# JJ_BLDC_v0_2b.net
KiCad netlist of a schematic drawn in EAGLE
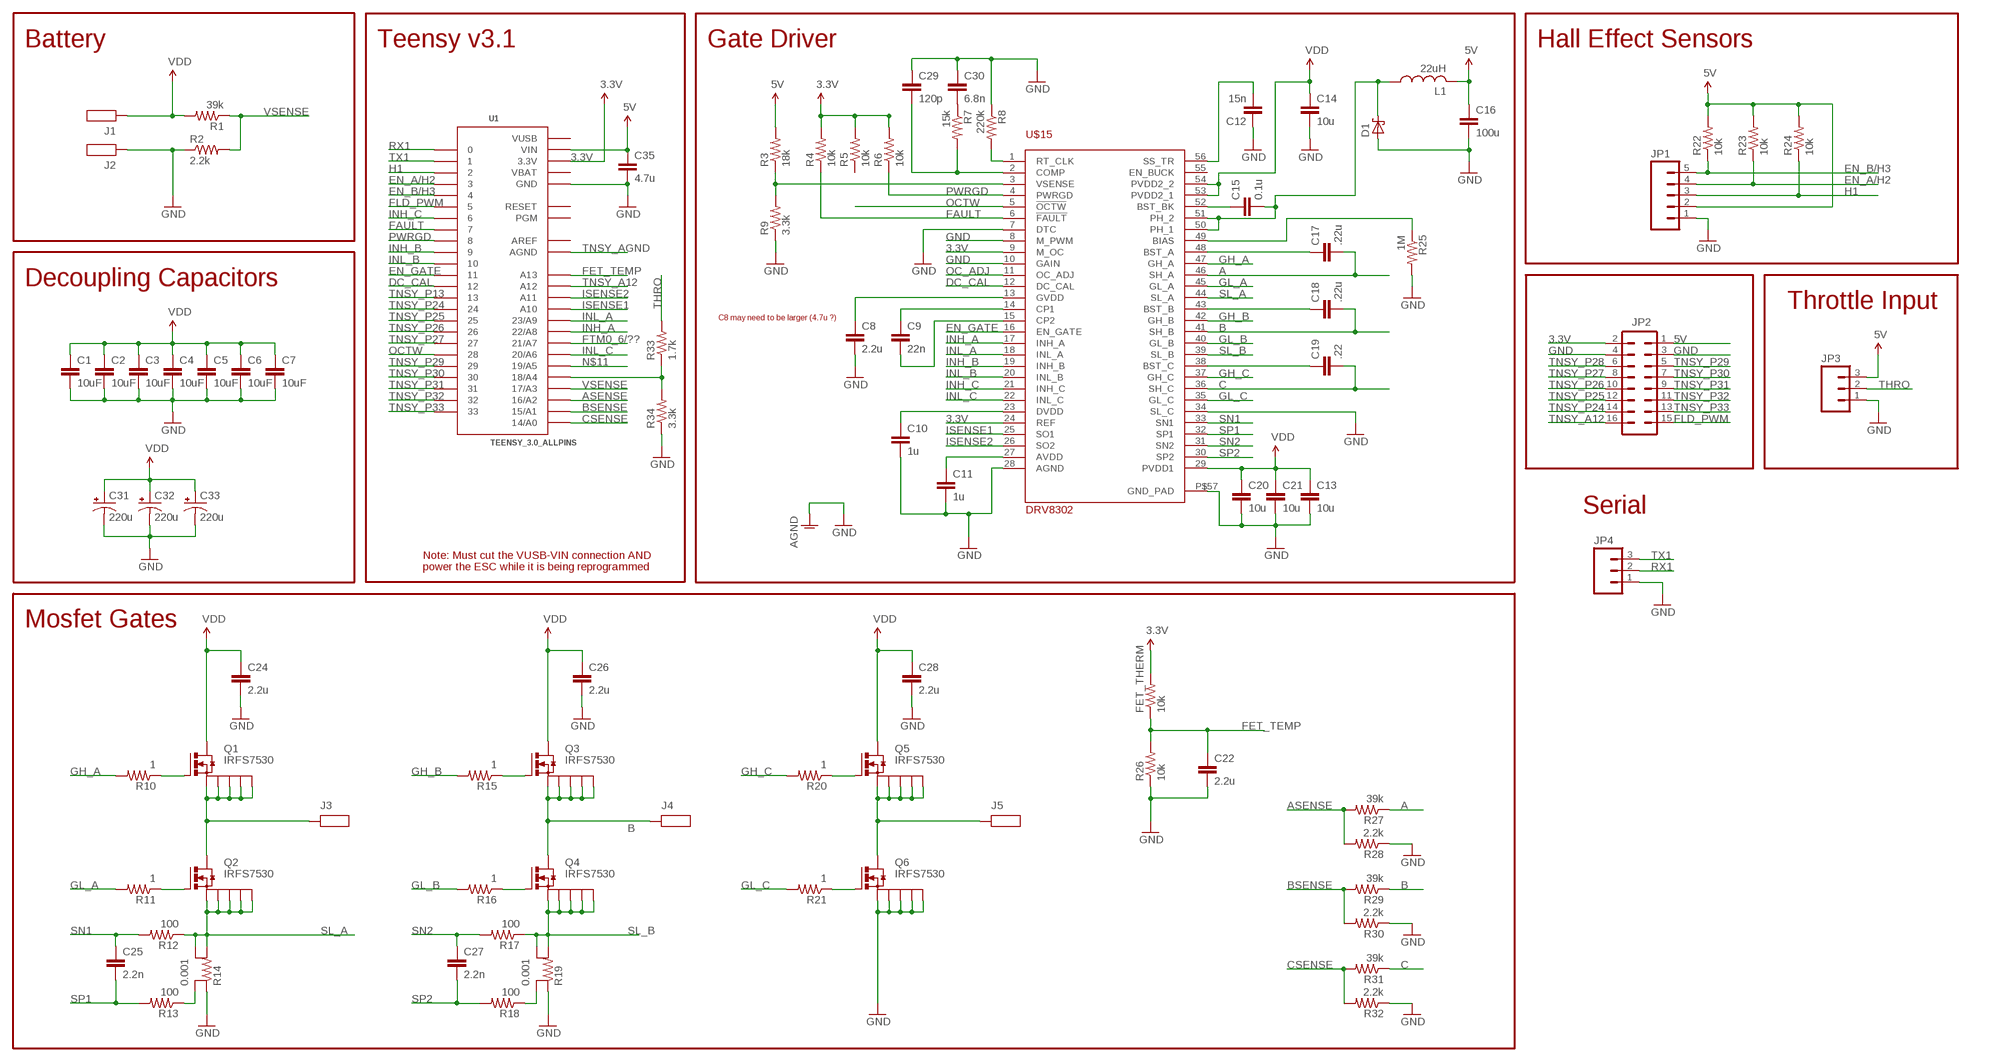
[diagram p0: schematic, sheet 1]

(export (version "E")
  (design (tool "Eeschema 10.0.6"))
  (components
    (comp (ref "C1")
      (value "10uF")
      (footprint "eagle-import:1206")
      (libsource (lib "eagle-import") (part "CAP1206"))
    )
    (comp (ref "C2")
      (value "10uF")
      (footprint "eagle-import:1206")
      (libsource (lib "eagle-import") (part "CAP1206"))
    )
    (comp (ref "C3")
      (value "10uF")
      (footprint "eagle-import:1206")
      (libsource (lib "eagle-import") (part "CAP1206"))
    )
    (comp (ref "C4")
      (value "10uF")
      (footprint "eagle-import:1206")
      (libsource (lib "eagle-import") (part "CAP1206"))
    )
    (comp (ref "C5")
      (value "10uF")
      (footprint "eagle-import:1206")
      (libsource (lib "eagle-import") (part "CAP1206"))
    )
    (comp (ref "C6")
      (value "10uF")
      (footprint "eagle-import:1206")
      (libsource (lib "eagle-import") (part "CAP1206"))
    )
    (comp (ref "C7")
      (value "10uF")
      (footprint "eagle-import:1206")
      (libsource (lib "eagle-import") (part "CAP1206"))
    )
    (comp (ref "C8")
      (value "2.2u")
      (footprint "eagle-import:0603-CAP")
      (libsource (lib "eagle-import") (part "CAP0603-CAP"))
    )
    (comp (ref "C9")
      (value "22n")
      (footprint "eagle-import:0603-CAP")
      (libsource (lib "eagle-import") (part "CAP0603-CAP"))
    )
    (comp (ref "C10")
      (value "1u")
      (footprint "eagle-import:0603-CAP")
      (libsource (lib "eagle-import") (part "CAP0603-CAP"))
    )
    (comp (ref "C11")
      (value "1u")
      (footprint "eagle-import:0603-CAP")
      (libsource (lib "eagle-import") (part "CAP0603-CAP"))
    )
    (comp (ref "C12")
      (value "15n")
      (footprint "eagle-import:0603-CAP")
      (libsource (lib "eagle-import") (part "CAP0603-CAP"))
    )
    (comp (ref "C13")
      (value "10u")
      (footprint "eagle-import:0805")
      (libsource (lib "eagle-import") (part "CAP0805"))
    )
    (comp (ref "C14")
      (value "10u")
      (footprint "eagle-import:0805")
      (libsource (lib "eagle-import") (part "CAP0805"))
    )
    (comp (ref "C15")
      (value "0.1u")
      (footprint "eagle-import:0603-CAP")
      (libsource (lib "eagle-import") (part "CAP0603-CAP"))
    )
    (comp (ref "C16")
      (value "100u")
      (footprint "eagle-import:0805")
      (libsource (lib "eagle-import") (part "CAP0805"))
    )
    (comp (ref "C17")
      (value ".22u")
      (footprint "eagle-import:0603-CAP")
      (libsource (lib "eagle-import") (part "CAP0603-CAP"))
    )
    (comp (ref "C18")
      (value ".22u")
      (footprint "eagle-import:0603-CAP")
      (libsource (lib "eagle-import") (part "CAP0603-CAP"))
    )
    (comp (ref "C19")
      (value ".22")
      (footprint "eagle-import:0603-CAP")
      (libsource (lib "eagle-import") (part "CAP0603-CAP"))
    )
    (comp (ref "C20")
      (value "10u")
      (footprint "eagle-import:0603-CAP")
      (libsource (lib "eagle-import") (part "CAP0603-CAP"))
    )
    (comp (ref "C21")
      (value "10u")
      (footprint "eagle-import:0805")
      (libsource (lib "eagle-import") (part "CAP0805"))
    )
    (comp (ref "C22")
      (value "2.2u")
      (footprint "eagle-import:0603-CAP")
      (libsource (lib "eagle-import") (part "CAP0603-CAP"))
    )
    (comp (ref "C24")
      (value "2.2u")
      (footprint "eagle-import:1206")
      (libsource (lib "eagle-import") (part "CAP1206"))
    )
    (comp (ref "C25")
      (value "2.2n")
      (footprint "eagle-import:0603-CAP")
      (libsource (lib "eagle-import") (part "CAP0603-CAP"))
    )
    (comp (ref "C26")
      (value "2.2u")
      (footprint "eagle-import:1206")
      (libsource (lib "eagle-import") (part "CAP1206"))
    )
    (comp (ref "C27")
      (value "2.2n")
      (footprint "eagle-import:0603-CAP")
      (libsource (lib "eagle-import") (part "CAP0603-CAP"))
    )
    (comp (ref "C28")
      (value "2.2u")
      (footprint "eagle-import:1206")
      (libsource (lib "eagle-import") (part "CAP1206"))
    )
    (comp (ref "C29")
      (value "120p")
      (footprint "eagle-import:0603-CAP")
      (libsource (lib "eagle-import") (part "CAP0603-CAP"))
    )
    (comp (ref "C30")
      (value "6.8n")
      (footprint "eagle-import:0603-CAP")
      (libsource (lib "eagle-import") (part "CAP0603-CAP"))
    )
    (comp (ref "C31")
      (value "220u")
      (footprint "eagle-import:E5-10,5")
      (libsource (lib "eagle-import") (part "CPOL-USE5-10.5"))
    )
    (comp (ref "C32")
      (value "220u")
      (footprint "eagle-import:E5-10,5")
      (libsource (lib "eagle-import") (part "CPOL-USE5-10.5"))
    )
    (comp (ref "C33")
      (value "220u")
      (footprint "eagle-import:E5-10,5")
      (libsource (lib "eagle-import") (part "CPOL-USE5-10.5"))
    )
    (comp (ref "C35")
      (value "4.7u")
      (footprint "eagle-import:0603-CAP")
      (libsource (lib "eagle-import") (part "CAP0603-CAP"))
    )
    (comp (ref "D1")
      (value "SCHOTTKY_SMA")
      (footprint "eagle-import:SMA")
      (libsource (lib "eagle-import") (part "SCHOTTKY_SMA"))
    )
    (comp (ref "FET_THERM")
      (value "10k")
      (footprint "eagle-import:0603-RES")
      (libsource (lib "eagle-import") (part "RESISTOR0603"))
    )
    (comp (ref "J1")
      (value "WIREPAD_SMD_10X4")
      (footprint "eagle-import:WIREPAD_SMD_10X4")
      (libsource (lib "eagle-import") (part "WIREPAD_SMD_10X4"))
    )
    (comp (ref "J2")
      (value "WIREPAD_SMD_10X4")
      (footprint "eagle-import:WIREPAD_SMD_10X4")
      (libsource (lib "eagle-import") (part "WIREPAD_SMD_10X4"))
    )
    (comp (ref "J3")
      (value "WIREPAD_SMD_10X4")
      (footprint "eagle-import:WIREPAD_SMD_10X4")
      (libsource (lib "eagle-import") (part "WIREPAD_SMD_10X4"))
    )
    (comp (ref "J4")
      (value "WIREPAD_SMD_10X4")
      (footprint "eagle-import:WIREPAD_SMD_10X4")
      (libsource (lib "eagle-import") (part "WIREPAD_SMD_10X4"))
    )
    (comp (ref "J5")
      (value "WIREPAD_SMD_10X4")
      (footprint "eagle-import:WIREPAD_SMD_10X4")
      (libsource (lib "eagle-import") (part "WIREPAD_SMD_10X4"))
    )
    (comp (ref "JP1")
      (value "M05PTH")
      (footprint "eagle-import:1X05")
      (libsource (lib "eagle-import") (part "M05PTH"))
    )
    (comp (ref "JP2")
      (value "M08X2")
      (footprint "eagle-import:2X8")
      (libsource (lib "eagle-import") (part "M08X2"))
    )
    (comp (ref "JP3")
      (value "M03PTH")
      (footprint "eagle-import:1X03")
      (libsource (lib "eagle-import") (part "M03PTH"))
    )
    (comp (ref "JP4")
      (value "M03PTH")
      (footprint "eagle-import:1X03")
      (libsource (lib "eagle-import") (part "M03PTH"))
    )
    (comp (ref "L1")
      (value "22uH")
      (footprint "eagle-import:L5650M")
      (libsource (lib "eagle-import") (part "L-USL5650M"))
    )
    (comp (ref "Q1")
      (value "IRFS7530")
      (footprint "eagle-import:TO-263-7")
      (libsource (lib "eagle-import") (part "IRFS7530"))
    )
    (comp (ref "Q2")
      (value "IRFS7530")
      (footprint "eagle-import:TO-263-7")
      (libsource (lib "eagle-import") (part "IRFS7530"))
    )
    (comp (ref "Q3")
      (value "IRFS7530")
      (footprint "eagle-import:TO-263-7")
      (libsource (lib "eagle-import") (part "IRFS7530"))
    )
    (comp (ref "Q4")
      (value "IRFS7530")
      (footprint "eagle-import:TO-263-7")
      (libsource (lib "eagle-import") (part "IRFS7530"))
    )
    (comp (ref "Q5")
      (value "IRFS7530")
      (footprint "eagle-import:TO-263-7")
      (libsource (lib "eagle-import") (part "IRFS7530"))
    )
    (comp (ref "Q6")
      (value "IRFS7530")
      (footprint "eagle-import:TO-263-7")
      (libsource (lib "eagle-import") (part "IRFS7530"))
    )
    (comp (ref "R1")
      (value "39k")
      (footprint "eagle-import:0603-RES")
      (libsource (lib "eagle-import") (part "RESISTOR0603"))
    )
    (comp (ref "R2")
      (value "2.2k")
      (footprint "eagle-import:0603-RES")
      (libsource (lib "eagle-import") (part "RESISTOR0603"))
    )
    (comp (ref "R3")
      (value "18k")
      (footprint "eagle-import:0603-RES")
      (libsource (lib "eagle-import") (part "RESISTOR0603"))
    )
    (comp (ref "R4")
      (value "10k")
      (footprint "eagle-import:0603-RES")
      (libsource (lib "eagle-import") (part "RESISTOR0603"))
    )
    (comp (ref "R5")
      (value "10k")
      (footprint "eagle-import:0603-RES")
      (libsource (lib "eagle-import") (part "RESISTOR0603"))
    )
    (comp (ref "R6")
      (value "10k")
      (footprint "eagle-import:0603-RES")
      (libsource (lib "eagle-import") (part "RESISTOR0603"))
    )
    (comp (ref "R7")
      (value "15k")
      (footprint "eagle-import:0603-RES")
      (libsource (lib "eagle-import") (part "RESISTOR0603"))
    )
    (comp (ref "R8")
      (value "220k")
      (footprint "eagle-import:0603-RES")
      (libsource (lib "eagle-import") (part "RESISTOR0603"))
    )
    (comp (ref "R9")
      (value "3.3k")
      (footprint "eagle-import:0603-RES")
      (libsource (lib "eagle-import") (part "RESISTOR0603"))
    )
    (comp (ref "R10")
      (value "1")
      (footprint "eagle-import:0603-RES")
      (libsource (lib "eagle-import") (part "RESISTOR0603"))
    )
    (comp (ref "R11")
      (value "1")
      (footprint "eagle-import:0603-RES")
      (libsource (lib "eagle-import") (part "RESISTOR0603"))
    )
    (comp (ref "R12")
      (value "100")
      (footprint "eagle-import:0603-RES")
      (libsource (lib "eagle-import") (part "RESISTOR0603"))
    )
    (comp (ref "R13")
      (value "100")
      (footprint "eagle-import:0603-RES")
      (libsource (lib "eagle-import") (part "RESISTOR0603"))
    )
    (comp (ref "R14")
      (value "0.001")
      (footprint "eagle-import:SHUNT-RES-2726")
      (libsource (lib "eagle-import") (part "WSLP2726_SHUNT"))
    )
    (comp (ref "R15")
      (value "1")
      (footprint "eagle-import:0603-RES")
      (libsource (lib "eagle-import") (part "RESISTOR0603"))
    )
    (comp (ref "R16")
      (value "1")
      (footprint "eagle-import:0603-RES")
      (libsource (lib "eagle-import") (part "RESISTOR0603"))
    )
    (comp (ref "R17")
      (value "100")
      (footprint "eagle-import:0603-RES")
      (libsource (lib "eagle-import") (part "RESISTOR0603"))
    )
    (comp (ref "R18")
      (value "100")
      (footprint "eagle-import:0603-RES")
      (libsource (lib "eagle-import") (part "RESISTOR0603"))
    )
    (comp (ref "R19")
      (value "0.001")
      (footprint "eagle-import:SHUNT-RES-2726")
      (libsource (lib "eagle-import") (part "WSLP2726_SHUNT"))
    )
    (comp (ref "R20")
      (value "1")
      (footprint "eagle-import:0603-RES")
      (libsource (lib "eagle-import") (part "RESISTOR0603"))
    )
    (comp (ref "R21")
      (value "1")
      (footprint "eagle-import:0603-RES")
      (libsource (lib "eagle-import") (part "RESISTOR0603"))
    )
    (comp (ref "R22")
      (value "10k")
      (footprint "eagle-import:0603-RES")
      (libsource (lib "eagle-import") (part "RESISTOR0603"))
    )
    (comp (ref "R23")
      (value "10k")
      (footprint "eagle-import:0603-RES")
      (libsource (lib "eagle-import") (part "RESISTOR0603"))
    )
    (comp (ref "R24")
      (value "10k")
      (footprint "eagle-import:0603-RES")
      (libsource (lib "eagle-import") (part "RESISTOR0603"))
    )
    (comp (ref "R25")
      (value "1M")
      (footprint "eagle-import:0603-RES")
      (libsource (lib "eagle-import") (part "RESISTOR0603"))
    )
    (comp (ref "R26")
      (value "10k")
      (footprint "eagle-import:0603-RES")
      (libsource (lib "eagle-import") (part "RESISTOR0603"))
    )
    (comp (ref "R27")
      (value "39k")
      (footprint "eagle-import:0603-RES")
      (libsource (lib "eagle-import") (part "RESISTOR0603"))
    )
    (comp (ref "R28")
      (value "2.2k")
      (footprint "eagle-import:0603-RES")
      (libsource (lib "eagle-import") (part "RESISTOR0603"))
    )
    (comp (ref "R29")
      (value "39k")
      (footprint "eagle-import:0603-RES")
      (libsource (lib "eagle-import") (part "RESISTOR0603"))
    )
    (comp (ref "R30")
      (value "2.2k")
      (footprint "eagle-import:0603-RES")
      (libsource (lib "eagle-import") (part "RESISTOR0603"))
    )
    (comp (ref "R31")
      (value "39k")
      (footprint "eagle-import:0603-RES")
      (libsource (lib "eagle-import") (part "RESISTOR0603"))
    )
    (comp (ref "R32")
      (value "2.2k")
      (footprint "eagle-import:0603-RES")
      (libsource (lib "eagle-import") (part "RESISTOR0603"))
    )
    (comp (ref "R33")
      (value "1.7k")
      (footprint "eagle-import:0603-RES")
      (libsource (lib "eagle-import") (part "RESISTOR0603"))
    )
    (comp (ref "R34")
      (value "3.3k")
      (footprint "eagle-import:0603-RES")
      (libsource (lib "eagle-import") (part "RESISTOR0603"))
    )
    (comp (ref "U$15")
      (value "DRV8302")
      (footprint "eagle-import:HTSSOP-56")
      (libsource (lib "eagle-import") (part "DRV8302"))
    )
    (comp (ref "U1")
      (value "TEENSY_3.0_ALLPINS")
      (footprint "eagle-import:TEENSY_3.0_ALLPINS")
      (libsource (lib "eagle-import") (part "TEENSY_3.0_ALLPINS"))
    )
  )
  (nets
    (net (code "1") (name "/A") (class "Default")
      (node (ref "C17") (pin "2") (pinfunction "2_2") (pintype "passive"))
      (node (ref "J3") (pin "P$1") (pinfunction "1_P$1") (pintype "bidirectional"))
      (node (ref "Q1") (pin "2") (pinfunction "S1_2") (pintype "output"))
      (node (ref "Q1") (pin "3") (pinfunction "S2_3") (pintype "output"))
      (node (ref "Q1") (pin "5") (pinfunction "S3_5") (pintype "output"))
      (node (ref "Q1") (pin "6") (pinfunction "S4_6") (pintype "output"))
      (node (ref "Q1") (pin "7") (pinfunction "S_7") (pintype "output"))
      (node (ref "Q2") (pin "4") (pinfunction "D_4") (pintype "input"))
      (node (ref "R27") (pin "1") (pinfunction "1_1") (pintype "passive"))
      (node (ref "U$15") (pin "46") (pinfunction "SH_A_46") (pintype "bidirectional"))
    )
    (net (code "2") (name "/AREF") (class "Default")
      (node (ref "U1") (pin "AREF") (pinfunction "AREF_AREF") (pintype "power_in"))
    )
    (net (code "3") (name "/ASENSE") (class "Default")
      (node (ref "R27") (pin "2") (pinfunction "2_2") (pintype "passive"))
      (node (ref "R28") (pin "2") (pinfunction "2_2") (pintype "passive"))
      (node (ref "U1") (pin "16/A2") (pinfunction "16/A2_16/A2") (pintype "bidirectional"))
    )
    (net (code "4") (name "/B") (class "Default")
      (node (ref "C18") (pin "2") (pinfunction "2_2") (pintype "passive"))
      (node (ref "J4") (pin "P$1") (pinfunction "1_P$1") (pintype "bidirectional"))
      (node (ref "Q3") (pin "2") (pinfunction "S1_2") (pintype "output"))
      (node (ref "Q3") (pin "3") (pinfunction "S2_3") (pintype "output"))
      (node (ref "Q3") (pin "5") (pinfunction "S3_5") (pintype "output"))
      (node (ref "Q3") (pin "6") (pinfunction "S4_6") (pintype "output"))
      (node (ref "Q3") (pin "7") (pinfunction "S_7") (pintype "output"))
      (node (ref "Q4") (pin "4") (pinfunction "D_4") (pintype "input"))
      (node (ref "R29") (pin "1") (pinfunction "1_1") (pintype "passive"))
      (node (ref "U$15") (pin "41") (pinfunction "SH_B_41") (pintype "bidirectional"))
    )
    (net (code "5") (name "/BSENSE") (class "Default")
      (node (ref "R29") (pin "2") (pinfunction "2_2") (pintype "passive"))
      (node (ref "R30") (pin "2") (pinfunction "2_2") (pintype "passive"))
      (node (ref "U1") (pin "15/A1") (pinfunction "15/A1_15/A1") (pintype "bidirectional"))
    )
    (net (code "6") (name "/C") (class "Default")
      (node (ref "C19") (pin "2") (pinfunction "2_2") (pintype "passive"))
      (node (ref "J5") (pin "P$1") (pinfunction "1_P$1") (pintype "bidirectional"))
      (node (ref "Q5") (pin "2") (pinfunction "S1_2") (pintype "output"))
      (node (ref "Q5") (pin "3") (pinfunction "S2_3") (pintype "output"))
      (node (ref "Q5") (pin "5") (pinfunction "S3_5") (pintype "output"))
      (node (ref "Q5") (pin "6") (pinfunction "S4_6") (pintype "output"))
      (node (ref "Q5") (pin "7") (pinfunction "S_7") (pintype "output"))
      (node (ref "Q6") (pin "4") (pinfunction "D_4") (pintype "input"))
      (node (ref "R31") (pin "1") (pinfunction "1_1") (pintype "passive"))
      (node (ref "U$15") (pin "36") (pinfunction "SH_C_36") (pintype "bidirectional"))
    )
    (net (code "7") (name "/CSENSE") (class "Default")
      (node (ref "R31") (pin "2") (pinfunction "2_2") (pintype "passive"))
      (node (ref "R32") (pin "2") (pinfunction "2_2") (pintype "passive"))
      (node (ref "U1") (pin "14/A0") (pinfunction "14/A0_14/A0") (pintype "bidirectional"))
    )
    (net (code "8") (name "/DC_CAL") (class "Default")
      (node (ref "U$15") (pin "12") (pinfunction "DC_CAL_12") (pintype "bidirectional"))
      (node (ref "U1") (pin "12") (pinfunction "12_12") (pintype "bidirectional"))
    )
    (net (code "9") (name "/EN_A{slash}H2") (class "Default")
      (node (ref "JP1") (pin "4") (pinfunction "4_4") (pintype "passive"))
      (node (ref "R23") (pin "1") (pinfunction "1_1") (pintype "passive"))
      (node (ref "U1") (pin "3") (pinfunction "3_3") (pintype "bidirectional"))
    )
    (net (code "10") (name "/EN_B{slash}H3") (class "Default")
      (node (ref "JP1") (pin "5") (pinfunction "5_5") (pintype "passive"))
      (node (ref "R22") (pin "1") (pinfunction "1_1") (pintype "passive"))
      (node (ref "U1") (pin "4") (pinfunction "4_4") (pintype "bidirectional"))
    )
    (net (code "11") (name "/EN_GATE") (class "Default")
      (node (ref "U$15") (pin "16") (pinfunction "EN_GATE_16") (pintype "bidirectional"))
      (node (ref "U1") (pin "11") (pinfunction "11_11") (pintype "bidirectional"))
    )
    (net (code "12") (name "/FAULT") (class "Default")
      (node (ref "R4") (pin "1") (pinfunction "1_1") (pintype "passive"))
      (node (ref "U$15") (pin "6") (pinfunction "~{FAULT}_6") (pintype "bidirectional"))
      (node (ref "U1") (pin "7") (pinfunction "7_7") (pintype "bidirectional"))
    )
    (net (code "13") (name "/FET_TEMP") (class "Default")
      (node (ref "C22") (pin "1") (pinfunction "1_1") (pintype "passive"))
      (node (ref "FET_THERM") (pin "1") (pinfunction "1_1") (pintype "passive"))
      (node (ref "R26") (pin "2") (pinfunction "2_2") (pintype "passive"))
      (node (ref "U1") (pin "A13") (pinfunction "A13_A13") (pintype "bidirectional"))
    )
    (net (code "14") (name "/FLD_PWM") (class "Default")
      (node (ref "JP2") (pin "15") (pinfunction "15_15") (pintype "passive"))
      (node (ref "U1") (pin "5") (pinfunction "5_5") (pintype "bidirectional"))
    )
    (net (code "15") (name "/FTM0_6{slash}??") (class "Default")
      (node (ref "U1") (pin "21/A7") (pinfunction "21/A7_21/A7") (pintype "bidirectional"))
    )
    (net (code "16") (name "/GH_A") (class "Default")
      (node (ref "R10") (pin "2") (pinfunction "2_2") (pintype "passive"))
      (node (ref "U$15") (pin "47") (pinfunction "GH_A_47") (pintype "bidirectional"))
    )
    (net (code "17") (name "/GH_B") (class "Default")
      (node (ref "R15") (pin "2") (pinfunction "2_2") (pintype "passive"))
      (node (ref "U$15") (pin "42") (pinfunction "GH_B_42") (pintype "bidirectional"))
    )
    (net (code "18") (name "/GH_C") (class "Default")
      (node (ref "R20") (pin "2") (pinfunction "2_2") (pintype "passive"))
      (node (ref "U$15") (pin "37") (pinfunction "GH_C_37") (pintype "bidirectional"))
    )
    (net (code "19") (name "/GL_A") (class "Default")
      (node (ref "R11") (pin "2") (pinfunction "2_2") (pintype "passive"))
      (node (ref "U$15") (pin "45") (pinfunction "GL_A_45") (pintype "bidirectional"))
    )
    (net (code "20") (name "/GL_B") (class "Default")
      (node (ref "R16") (pin "2") (pinfunction "2_2") (pintype "passive"))
      (node (ref "U$15") (pin "40") (pinfunction "GL_B_40") (pintype "bidirectional"))
    )
    (net (code "21") (name "/GL_C") (class "Default")
      (node (ref "R21") (pin "2") (pinfunction "2_2") (pintype "passive"))
      (node (ref "U$15") (pin "35") (pinfunction "GL_C_35") (pintype "bidirectional"))
    )
    (net (code "22") (name "/H1") (class "Default")
      (node (ref "JP1") (pin "3") (pinfunction "3_3") (pintype "passive"))
      (node (ref "R24") (pin "1") (pinfunction "1_1") (pintype "passive"))
      (node (ref "U1") (pin "2") (pinfunction "2_2") (pintype "bidirectional"))
    )
    (net (code "23") (name "/INH_A") (class "Default")
      (node (ref "U$15") (pin "17") (pinfunction "INH_A_17") (pintype "bidirectional"))
      (node (ref "U1") (pin "22/A8") (pinfunction "22/A8_22/A8") (pintype "bidirectional"))
    )
    (net (code "24") (name "/INH_B") (class "Default")
      (node (ref "U$15") (pin "19") (pinfunction "INH_B_19") (pintype "bidirectional"))
      (node (ref "U1") (pin "9") (pinfunction "9_9") (pintype "bidirectional"))
    )
    (net (code "25") (name "/INH_C") (class "Default")
      (node (ref "U$15") (pin "21") (pinfunction "INH_C_21") (pintype "bidirectional"))
      (node (ref "U1") (pin "6") (pinfunction "6_6") (pintype "bidirectional"))
    )
    (net (code "26") (name "/INL_A") (class "Default")
      (node (ref "U$15") (pin "18") (pinfunction "INL_A_18") (pintype "bidirectional"))
      (node (ref "U1") (pin "23/A9") (pinfunction "23/A9_23/A9") (pintype "bidirectional"))
    )
    (net (code "27") (name "/INL_B") (class "Default")
      (node (ref "U$15") (pin "20") (pinfunction "INL_B_20") (pintype "bidirectional"))
      (node (ref "U1") (pin "10") (pinfunction "10_10") (pintype "bidirectional"))
    )
    (net (code "28") (name "/INL_C") (class "Default")
      (node (ref "U$15") (pin "22") (pinfunction "INL_C_22") (pintype "bidirectional"))
      (node (ref "U1") (pin "20/A6") (pinfunction "20/A6_20/A6") (pintype "bidirectional"))
    )
    (net (code "29") (name "/ISENSE1") (class "Default")
      (node (ref "U$15") (pin "25") (pinfunction "SO1_25") (pintype "bidirectional"))
      (node (ref "U1") (pin "A10") (pinfunction "A10_A10") (pintype "bidirectional"))
    )
    (net (code "30") (name "/ISENSE2") (class "Default")
      (node (ref "U$15") (pin "26") (pinfunction "SO2_26") (pintype "bidirectional"))
      (node (ref "U1") (pin "A11") (pinfunction "A11_A11") (pintype "bidirectional"))
    )
    (net (code "31") (name "/N$11") (class "Default")
      (node (ref "U1") (pin "19/A5") (pinfunction "19/A5_19/A5") (pintype "bidirectional"))
    )
    (net (code "32") (name "/OCTW") (class "Default")
      (node (ref "U$15") (pin "5") (pinfunction "~{OCTW}_5") (pintype "bidirectional"))
      (node (ref "U1") (pin "28") (pinfunction "28_28") (pintype "bidirectional"))
    )
    (net (code "33") (name "/OC_ADJ") (class "Default")
      (node (ref "U$15") (pin "11") (pinfunction "OC_ADJ_11") (pintype "bidirectional"))
    )
    (net (code "34") (name "/PWRGD") (class "Default")
      (node (ref "R6") (pin "1") (pinfunction "1_1") (pintype "passive"))
      (node (ref "U$15") (pin "4") (pinfunction "PWRGD_4") (pintype "bidirectional"))
      (node (ref "U1") (pin "8") (pinfunction "8_8") (pintype "bidirectional"))
    )
    (net (code "35") (name "/RX1") (class "Default")
      (node (ref "JP4") (pin "2") (pinfunction "2_2") (pintype "passive"))
      (node (ref "U1") (pin "0") (pinfunction "0_0") (pintype "bidirectional"))
    )
    (net (code "36") (name "/SL_A") (class "Default")
      (node (ref "Q2") (pin "2") (pinfunction "S1_2") (pintype "output"))
      (node (ref "Q2") (pin "3") (pinfunction "S2_3") (pintype "output"))
      (node (ref "Q2") (pin "5") (pinfunction "S3_5") (pintype "output"))
      (node (ref "Q2") (pin "6") (pinfunction "S4_6") (pintype "output"))
      (node (ref "Q2") (pin "7") (pinfunction "S_7") (pintype "output"))
      (node (ref "R12") (pin "1") (pinfunction "1_1") (pintype "passive"))
      (node (ref "R14") (pin "P$2") (pinfunction "2_P$2") (pintype "bidirectional"))
      (node (ref "R14") (pin "P$4") (pinfunction "P$2_P$4") (pintype "bidirectional"))
      (node (ref "U$15") (pin "44") (pinfunction "SL_A_44") (pintype "bidirectional"))
    )
    (net (code "37") (name "/SL_B") (class "Default")
      (node (ref "Q4") (pin "2") (pinfunction "S1_2") (pintype "output"))
      (node (ref "Q4") (pin "3") (pinfunction "S2_3") (pintype "output"))
      (node (ref "Q4") (pin "5") (pinfunction "S3_5") (pintype "output"))
      (node (ref "Q4") (pin "6") (pinfunction "S4_6") (pintype "output"))
      (node (ref "Q4") (pin "7") (pinfunction "S_7") (pintype "output"))
      (node (ref "R17") (pin "1") (pinfunction "1_1") (pintype "passive"))
      (node (ref "R19") (pin "P$2") (pinfunction "2_P$2") (pintype "bidirectional"))
      (node (ref "R19") (pin "P$4") (pinfunction "P$2_P$4") (pintype "bidirectional"))
      (node (ref "U$15") (pin "39") (pinfunction "SL_B_39") (pintype "bidirectional"))
    )
    (net (code "38") (name "/SN1") (class "Default")
      (node (ref "C25") (pin "1") (pinfunction "1_1") (pintype "passive"))
      (node (ref "R12") (pin "2") (pinfunction "2_2") (pintype "passive"))
      (node (ref "U$15") (pin "33") (pinfunction "SN1_33") (pintype "bidirectional"))
    )
    (net (code "39") (name "/SN2") (class "Default")
      (node (ref "C27") (pin "1") (pinfunction "1_1") (pintype "passive"))
      (node (ref "R17") (pin "2") (pinfunction "2_2") (pintype "passive"))
      (node (ref "U$15") (pin "31") (pinfunction "SN2_31") (pintype "bidirectional"))
    )
    (net (code "40") (name "/SP1") (class "Default")
      (node (ref "C25") (pin "2") (pinfunction "2_2") (pintype "passive"))
      (node (ref "R13") (pin "2") (pinfunction "2_2") (pintype "passive"))
      (node (ref "U$15") (pin "32") (pinfunction "SP1_32") (pintype "bidirectional"))
    )
    (net (code "41") (name "/SP2") (class "Default")
      (node (ref "C27") (pin "2") (pinfunction "2_2") (pintype "passive"))
      (node (ref "R18") (pin "2") (pinfunction "2_2") (pintype "passive"))
      (node (ref "U$15") (pin "30") (pinfunction "SP2_30") (pintype "bidirectional"))
    )
    (net (code "42") (name "/THRO") (class "Default")
      (node (ref "JP3") (pin "2") (pinfunction "2_2") (pintype "passive"))
      (node (ref "R33") (pin "2") (pinfunction "2_2") (pintype "passive"))
    )
    (net (code "43") (name "/TNSY_A12") (class "Default")
      (node (ref "JP2") (pin "16") (pinfunction "16_16") (pintype "passive"))
      (node (ref "U1") (pin "A12") (pinfunction "A12_A12") (pintype "bidirectional"))
    )
    (net (code "44") (name "/TNSY_AGND") (class "Default")
      (node (ref "U1") (pin "AGND") (pinfunction "AGND_AGND") (pintype "power_in"))
    )
    (net (code "45") (name "/TNSY_P13") (class "Default")
      (node (ref "U1") (pin "13") (pinfunction "13_13") (pintype "bidirectional"))
    )
    (net (code "46") (name "/TNSY_P24") (class "Default")
      (node (ref "JP2") (pin "14") (pinfunction "14_14") (pintype "passive"))
      (node (ref "U1") (pin "24") (pinfunction "24_24") (pintype "bidirectional"))
    )
    (net (code "47") (name "/TNSY_P25") (class "Default")
      (node (ref "JP2") (pin "12") (pinfunction "12_12") (pintype "passive"))
      (node (ref "U1") (pin "25") (pinfunction "25_25") (pintype "bidirectional"))
    )
    (net (code "48") (name "/TNSY_P26") (class "Default")
      (node (ref "JP2") (pin "10") (pinfunction "10_10") (pintype "passive"))
      (node (ref "U1") (pin "26") (pinfunction "26_26") (pintype "bidirectional"))
    )
    (net (code "49") (name "/TNSY_P27") (class "Default")
      (node (ref "JP2") (pin "8") (pinfunction "8_8") (pintype "passive"))
      (node (ref "U1") (pin "27") (pinfunction "27_27") (pintype "bidirectional"))
    )
    (net (code "50") (name "/TNSY_P28") (class "Default")
      (node (ref "JP2") (pin "6") (pinfunction "6_6") (pintype "passive"))
    )
    (net (code "51") (name "/TNSY_P29") (class "Default")
      (node (ref "JP2") (pin "5") (pinfunction "5_5") (pintype "passive"))
      (node (ref "U1") (pin "29") (pinfunction "29_29") (pintype "bidirectional"))
    )
    (net (code "52") (name "/TNSY_P30") (class "Default")
      (node (ref "JP2") (pin "7") (pinfunction "7_7") (pintype "passive"))
      (node (ref "U1") (pin "30") (pinfunction "30_30") (pintype "bidirectional"))
    )
    (net (code "53") (name "/TNSY_P31") (class "Default")
      (node (ref "JP2") (pin "9") (pinfunction "9_9") (pintype "passive"))
      (node (ref "U1") (pin "31") (pinfunction "31_31") (pintype "bidirectional"))
    )
    (net (code "54") (name "/TNSY_P32") (class "Default")
      (node (ref "JP2") (pin "11") (pinfunction "11_11") (pintype "passive"))
      (node (ref "U1") (pin "32") (pinfunction "32_32") (pintype "bidirectional"))
    )
    (net (code "55") (name "/TNSY_P33") (class "Default")
      (node (ref "JP2") (pin "13") (pinfunction "13_13") (pintype "passive"))
      (node (ref "U1") (pin "33") (pinfunction "33_33") (pintype "bidirectional"))
    )
    (net (code "56") (name "/TX1") (class "Default")
      (node (ref "JP4") (pin "3") (pinfunction "3_3") (pintype "passive"))
      (node (ref "U1") (pin "1") (pinfunction "1_1") (pintype "bidirectional"))
    )
    (net (code "57") (name "/VBAT") (class "Default")
      (node (ref "U1") (pin "VBAT") (pinfunction "VBAT_VBAT") (pintype "power_in"))
    )
    (net (code "58") (name "/VSENSE") (class "Default")
      (node (ref "R1") (pin "1") (pinfunction "1_1") (pintype "passive"))
      (node (ref "R2") (pin "2") (pinfunction "2_2") (pintype "passive"))
      (node (ref "U1") (pin "17/A3") (pinfunction "17/A3_17/A3") (pintype "bidirectional"))
    )
    (net (code "59") (name "/VUSB") (class "Default")
      (node (ref "U1") (pin "VUSB") (pinfunction "VUSB_VUSB") (pintype "power_in"))
    )
    (net (code "60") (name "3.3V") (class "Default")
      (node (ref "FET_THERM") (pin "2") (pinfunction "2_2") (pintype "passive"))
      (node (ref "JP2") (pin "2") (pinfunction "2_2") (pintype "passive"))
      (node (ref "R4") (pin "2") (pinfunction "2_2") (pintype "passive"))
      (node (ref "R5") (pin "2") (pinfunction "2_2") (pintype "passive"))
      (node (ref "R6") (pin "2") (pinfunction "2_2") (pintype "passive"))
      (node (ref "U$15") (pin "24") (pinfunction "REF_24") (pintype "bidirectional"))
      (node (ref "U$15") (pin "9") (pinfunction "M_OC_9") (pintype "bidirectional"))
      (node (ref "U1") (pin "3.3V") (pinfunction "3.3V_3.3V") (pintype "power_in"))
      (node (ref "U1") (pin "3.3V1") (pinfunction "3.3V_3.3V1") (pintype "power_in"))
      (node (ref "U1") (pin "3.3V2") (pinfunction "3.3V_3.3V2") (pintype "power_in"))
    )
    (net (code "61") (name "5V") (class "Default")
      (node (ref "C16") (pin "1") (pinfunction "1_1") (pintype "passive"))
      (node (ref "C35") (pin "1") (pinfunction "1_1") (pintype "passive"))
      (node (ref "JP1") (pin "2") (pinfunction "2_2") (pintype "passive"))
      (node (ref "JP2") (pin "1") (pinfunction "1_1") (pintype "passive"))
      (node (ref "JP3") (pin "3") (pinfunction "3_3") (pintype "passive"))
      (node (ref "L1") (pin "2") (pinfunction "2_2") (pintype "passive"))
      (node (ref "R22") (pin "2") (pinfunction "2_2") (pintype "passive"))
      (node (ref "R23") (pin "2") (pinfunction "2_2") (pintype "passive"))
      (node (ref "R24") (pin "2") (pinfunction "2_2") (pintype "passive"))
      (node (ref "R3") (pin "2") (pinfunction "2_2") (pintype "passive"))
      (node (ref "U1") (pin "VIN") (pinfunction "VIN_VIN") (pintype "power_in"))
    )
    (net (code "62") (name "AGND") (class "Default")
      (node (ref "C1") (pin "2") (pinfunction "2_2") (pintype "passive"))
      (node (ref "C10") (pin "2") (pinfunction "2_2") (pintype "passive"))
      (node (ref "C11") (pin "2") (pinfunction "2_2") (pintype "passive"))
      (node (ref "C12") (pin "1") (pinfunction "1_1") (pintype "passive"))
      (node (ref "C13") (pin "2") (pinfunction "2_2") (pintype "passive"))
      (node (ref "C14") (pin "2") (pinfunction "2_2") (pintype "passive"))
      (node (ref "C16") (pin "2") (pinfunction "2_2") (pintype "passive"))
      (node (ref "C2") (pin "2") (pinfunction "2_2") (pintype "passive"))
      (node (ref "C20") (pin "2") (pinfunction "2_2") (pintype "passive"))
      (node (ref "C21") (pin "2") (pinfunction "2_2") (pintype "passive"))
      (node (ref "C22") (pin "2") (pinfunction "2_2") (pintype "passive"))
      (node (ref "C24") (pin "2") (pinfunction "2_2") (pintype "passive"))
      (node (ref "C26") (pin "2") (pinfunction "2_2") (pintype "passive"))
      (node (ref "C28") (pin "2") (pinfunction "2_2") (pintype "passive"))
      (node (ref "C29") (pin "1") (pinfunction "1_1") (pintype "passive"))
      (node (ref "C3") (pin "2") (pinfunction "2_2") (pintype "passive"))
      (node (ref "C30") (pin "1") (pinfunction "1_1") (pintype "passive"))
      (node (ref "C31") (pin "-") (pinfunction "-_-") (pintype "passive"))
      (node (ref "C32") (pin "-") (pinfunction "-_-") (pintype "passive"))
      (node (ref "C33") (pin "-") (pinfunction "-_-") (pintype "passive"))
      (node (ref "C35") (pin "2") (pinfunction "2_2") (pintype "passive"))
      (node (ref "C4") (pin "2") (pinfunction "2_2") (pintype "passive"))
      (node (ref "C5") (pin "2") (pinfunction "2_2") (pintype "passive"))
      (node (ref "C6") (pin "2") (pinfunction "2_2") (pintype "passive"))
      (node (ref "C7") (pin "2") (pinfunction "2_2") (pintype "passive"))
      (node (ref "C8") (pin "2") (pinfunction "2_2") (pintype "passive"))
      (node (ref "D1") (pin "A") (pinfunction "A_A") (pintype "passive"))
      (node (ref "J2") (pin "P$1") (pinfunction "1_P$1") (pintype "bidirectional"))
      (node (ref "JP1") (pin "1") (pinfunction "1_1") (pintype "passive"))
      (node (ref "JP2") (pin "3") (pinfunction "3_3") (pintype "passive"))
      (node (ref "JP2") (pin "4") (pinfunction "4_4") (pintype "passive"))
      (node (ref "JP3") (pin "1") (pinfunction "1_1") (pintype "passive"))
      (node (ref "JP4") (pin "1") (pinfunction "1_1") (pintype "passive"))
      (node (ref "Q6") (pin "2") (pinfunction "S1_2") (pintype "output"))
      (node (ref "Q6") (pin "3") (pinfunction "S2_3") (pintype "output"))
      (node (ref "Q6") (pin "5") (pinfunction "S3_5") (pintype "output"))
      (node (ref "Q6") (pin "6") (pinfunction "S4_6") (pintype "output"))
      (node (ref "Q6") (pin "7") (pinfunction "S_7") (pintype "output"))
      (node (ref "R14") (pin "P$1") (pinfunction "1_P$1") (pintype "bidirectional"))
      (node (ref "R19") (pin "P$1") (pinfunction "1_P$1") (pintype "bidirectional"))
      (node (ref "R2") (pin "1") (pinfunction "1_1") (pintype "passive"))
      (node (ref "R25") (pin "2") (pinfunction "2_2") (pintype "passive"))
      (node (ref "R26") (pin "1") (pinfunction "1_1") (pintype "passive"))
      (node (ref "R28") (pin "1") (pinfunction "1_1") (pintype "passive"))
      (node (ref "R30") (pin "1") (pinfunction "1_1") (pintype "passive"))
      (node (ref "R32") (pin "1") (pinfunction "1_1") (pintype "passive"))
      (node (ref "R34") (pin "1") (pinfunction "1_1") (pintype "passive"))
      (node (ref "R8") (pin "1") (pinfunction "1_1") (pintype "passive"))
      (node (ref "R9") (pin "1") (pinfunction "1_1") (pintype "passive"))
      (node (ref "U$15") (pin "10") (pinfunction "GAIN_10") (pintype "bidirectional"))
      (node (ref "U$15") (pin "28") (pinfunction "AGND_28") (pintype "bidirectional"))
      (node (ref "U$15") (pin "34") (pinfunction "SL_C_34") (pintype "bidirectional"))
      (node (ref "U$15") (pin "7") (pinfunction "DTC_7") (pintype "bidirectional"))
      (node (ref "U$15") (pin "8") (pinfunction "M_PWM_8") (pintype "bidirectional"))
      (node (ref "U$15") (pin "P$57") (pinfunction "GND_PAD_P$57") (pintype "bidirectional"))
      (node (ref "U1") (pin "GND") (pinfunction "GND_GND") (pintype "power_in"))
      (node (ref "U1") (pin "GND1") (pinfunction "GND_GND1") (pintype "power_in"))
      (node (ref "U1") (pin "GND2") (pinfunction "GND_GND2") (pintype "power_in"))
    )
    (net (code "63") (name "Net-(C30-Pad2)") (class "Default")
      (node (ref "C30") (pin "2") (pinfunction "2_2") (pintype "passive"))
      (node (ref "R7") (pin "1") (pinfunction "1_1") (pintype "passive"))
    )
    (net (code "64") (name "Net-(Q1-G)") (class "Default")
      (node (ref "Q1") (pin "1") (pinfunction "G_1") (pintype "input"))
      (node (ref "R10") (pin "1") (pinfunction "1_1") (pintype "passive"))
    )
    (net (code "65") (name "Net-(Q2-G)") (class "Default")
      (node (ref "Q2") (pin "1") (pinfunction "G_1") (pintype "input"))
      (node (ref "R11") (pin "1") (pinfunction "1_1") (pintype "passive"))
    )
    (net (code "66") (name "Net-(Q3-G)") (class "Default")
      (node (ref "Q3") (pin "1") (pinfunction "G_1") (pintype "input"))
      (node (ref "R15") (pin "1") (pinfunction "1_1") (pintype "passive"))
    )
    (net (code "67") (name "Net-(Q4-G)") (class "Default")
      (node (ref "Q4") (pin "1") (pinfunction "G_1") (pintype "input"))
      (node (ref "R16") (pin "1") (pinfunction "1_1") (pintype "passive"))
    )
    (net (code "68") (name "Net-(Q5-G)") (class "Default")
      (node (ref "Q5") (pin "1") (pinfunction "G_1") (pintype "input"))
      (node (ref "R20") (pin "1") (pinfunction "1_1") (pintype "passive"))
    )
    (net (code "69") (name "Net-(Q6-G)") (class "Default")
      (node (ref "Q6") (pin "1") (pinfunction "G_1") (pintype "input"))
      (node (ref "R21") (pin "1") (pinfunction "1_1") (pintype "passive"))
    )
    (net (code "70") (name "Net-(R14-P$1)") (class "Default")
      (node (ref "R13") (pin "1") (pinfunction "1_1") (pintype "passive"))
      (node (ref "R14") (pin "P$3") (pinfunction "P$1_P$3") (pintype "bidirectional"))
    )
    (net (code "71") (name "Net-(R19-P$1)") (class "Default")
      (node (ref "R18") (pin "1") (pinfunction "1_1") (pintype "passive"))
      (node (ref "R19") (pin "P$3") (pinfunction "P$1_P$3") (pintype "bidirectional"))
    )
    (net (code "72") (name "Net-(R33-Pad1)") (class "Default")
      (node (ref "R33") (pin "1") (pinfunction "1_1") (pintype "passive"))
      (node (ref "R34") (pin "2") (pinfunction "2_2") (pintype "passive"))
      (node (ref "U1") (pin "18/A4") (pinfunction "18/A4_18/A4") (pintype "bidirectional"))
    )
    (net (code "73") (name "Net-(U$15-AVDD)") (class "Default")
      (node (ref "C11") (pin "1") (pinfunction "1_1") (pintype "passive"))
      (node (ref "U$15") (pin "27") (pinfunction "AVDD_27") (pintype "bidirectional"))
    )
    (net (code "74") (name "Net-(U$15-BIAS)") (class "Default")
      (node (ref "R25") (pin "1") (pinfunction "1_1") (pintype "passive"))
      (node (ref "U$15") (pin "49") (pinfunction "BIAS_49") (pintype "bidirectional"))
    )
    (net (code "75") (name "Net-(U$15-BST_A)") (class "Default")
      (node (ref "C17") (pin "1") (pinfunction "1_1") (pintype "passive"))
      (node (ref "U$15") (pin "48") (pinfunction "BST_A_48") (pintype "bidirectional"))
    )
    (net (code "76") (name "Net-(U$15-BST_B)") (class "Default")
      (node (ref "C18") (pin "1") (pinfunction "1_1") (pintype "passive"))
      (node (ref "U$15") (pin "43") (pinfunction "BST_B_43") (pintype "bidirectional"))
    )
    (net (code "77") (name "Net-(U$15-BST_BK)") (class "Default")
      (node (ref "C15") (pin "1") (pinfunction "1_1") (pintype "passive"))
      (node (ref "U$15") (pin "52") (pinfunction "BST_BK_52") (pintype "bidirectional"))
    )
    (net (code "78") (name "Net-(U$15-BST_C)") (class "Default")
      (node (ref "C19") (pin "1") (pinfunction "1_1") (pintype "passive"))
      (node (ref "U$15") (pin "38") (pinfunction "BST_C_38") (pintype "bidirectional"))
    )
    (net (code "79") (name "Net-(U$15-COMP)") (class "Default")
      (node (ref "C29") (pin "2") (pinfunction "2_2") (pintype "passive"))
      (node (ref "R7") (pin "2") (pinfunction "2_2") (pintype "passive"))
      (node (ref "U$15") (pin "2") (pinfunction "COMP_2") (pintype "bidirectional"))
    )
    (net (code "80") (name "Net-(U$15-CP1)") (class "Default")
      (node (ref "C9") (pin "1") (pinfunction "1_1") (pintype "passive"))
      (node (ref "U$15") (pin "14") (pinfunction "CP1_14") (pintype "bidirectional"))
    )
    (net (code "81") (name "Net-(U$15-CP2)") (class "Default")
      (node (ref "C9") (pin "2") (pinfunction "2_2") (pintype "passive"))
      (node (ref "U$15") (pin "15") (pinfunction "CP2_15") (pintype "bidirectional"))
    )
    (net (code "82") (name "Net-(U$15-DVDD)") (class "Default")
      (node (ref "C10") (pin "1") (pinfunction "1_1") (pintype "passive"))
      (node (ref "U$15") (pin "23") (pinfunction "DVDD_23") (pintype "bidirectional"))
    )
    (net (code "83") (name "Net-(U$15-GVDD)") (class "Default")
      (node (ref "C8") (pin "1") (pinfunction "1_1") (pintype "passive"))
      (node (ref "U$15") (pin "13") (pinfunction "GVDD_13") (pintype "bidirectional"))
    )
    (net (code "84") (name "Net-(U$15-PH_1)") (class "Default")
      (node (ref "C15") (pin "2") (pinfunction "2_2") (pintype "passive"))
      (node (ref "D1") (pin "C") (pinfunction "C_C") (pintype "passive"))
      (node (ref "L1") (pin "1") (pinfunction "1_1") (pintype "passive"))
      (node (ref "U$15") (pin "50") (pinfunction "PH_1_50") (pintype "bidirectional"))
      (node (ref "U$15") (pin "51") (pinfunction "PH_2_51") (pintype "bidirectional"))
    )
    (net (code "85") (name "Net-(U$15-RT_CLK)") (class "Default")
      (node (ref "R8") (pin "2") (pinfunction "2_2") (pintype "passive"))
      (node (ref "U$15") (pin "1") (pinfunction "RT_CLK_1") (pintype "bidirectional"))
    )
    (net (code "86") (name "Net-(U$15-SS_TR)") (class "Default")
      (node (ref "C12") (pin "2") (pinfunction "2_2") (pintype "passive"))
      (node (ref "U$15") (pin "56") (pinfunction "SS_TR_56") (pintype "bidirectional"))
    )
    (net (code "87") (name "Net-(U$15-VSENSE)") (class "Default")
      (node (ref "R3") (pin "1") (pinfunction "1_1") (pintype "passive"))
      (node (ref "R9") (pin "2") (pinfunction "2_2") (pintype "passive"))
      (node (ref "U$15") (pin "3") (pinfunction "VSENSE_3") (pintype "bidirectional"))
    )
    (net (code "88") (name "VDD") (class "Default")
      (node (ref "C1") (pin "1") (pinfunction "1_1") (pintype "passive"))
      (node (ref "C13") (pin "1") (pinfunction "1_1") (pintype "passive"))
      (node (ref "C14") (pin "1") (pinfunction "1_1") (pintype "passive"))
      (node (ref "C2") (pin "1") (pinfunction "1_1") (pintype "passive"))
      (node (ref "C20") (pin "1") (pinfunction "1_1") (pintype "passive"))
      (node (ref "C21") (pin "1") (pinfunction "1_1") (pintype "passive"))
      (node (ref "C24") (pin "1") (pinfunction "1_1") (pintype "passive"))
      (node (ref "C26") (pin "1") (pinfunction "1_1") (pintype "passive"))
      (node (ref "C28") (pin "1") (pinfunction "1_1") (pintype "passive"))
      (node (ref "C3") (pin "1") (pinfunction "1_1") (pintype "passive"))
      (node (ref "C31") (pin "+") (pinfunction "+_+") (pintype "passive"))
      (node (ref "C32") (pin "+") (pinfunction "+_+") (pintype "passive"))
      (node (ref "C33") (pin "+") (pinfunction "+_+") (pintype "passive"))
      (node (ref "C4") (pin "1") (pinfunction "1_1") (pintype "passive"))
      (node (ref "C5") (pin "1") (pinfunction "1_1") (pintype "passive"))
      (node (ref "C6") (pin "1") (pinfunction "1_1") (pintype "passive"))
      (node (ref "C7") (pin "1") (pinfunction "1_1") (pintype "passive"))
      (node (ref "J1") (pin "P$1") (pinfunction "1_P$1") (pintype "bidirectional"))
      (node (ref "Q1") (pin "4") (pinfunction "D_4") (pintype "input"))
      (node (ref "Q3") (pin "4") (pinfunction "D_4") (pintype "input"))
      (node (ref "Q5") (pin "4") (pinfunction "D_4") (pintype "input"))
      (node (ref "R1") (pin "2") (pinfunction "2_2") (pintype "passive"))
      (node (ref "U$15") (pin "29") (pinfunction "PVDD1_29") (pintype "bidirectional"))
      (node (ref "U$15") (pin "53") (pinfunction "PVDD2_1_53") (pintype "bidirectional"))
      (node (ref "U$15") (pin "54") (pinfunction "PVDD2_2_54") (pintype "bidirectional"))
    )
    (net (code "89") (name "unconnected-(R5-Pad1)") (class "Default")
      (node (ref "R5") (pin "1") (pinfunction "1_1") (pintype "passive"))
    )
    (net (code "90") (name "unconnected-(U$15-EN_BUCK-Pad55)") (class "Default")
      (node (ref "U$15") (pin "55") (pinfunction "EN_BUCK_55") (pintype "bidirectional"))
    )
    (net (code "91") (name "unconnected-(U1-PadPGM)") (class "Default")
      (node (ref "U1") (pin "PGM") (pinfunction "PGM_PGM") (pintype "bidirectional"))
    )
    (net (code "92") (name "unconnected-(U1-PadRESET)") (class "Default")
      (node (ref "U1") (pin "RESET") (pinfunction "RESET_RESET") (pintype "bidirectional"))
    )
  )
)
